# FP_Connectors.net
KiCad netlist of a schematic drawn in Altium Designer
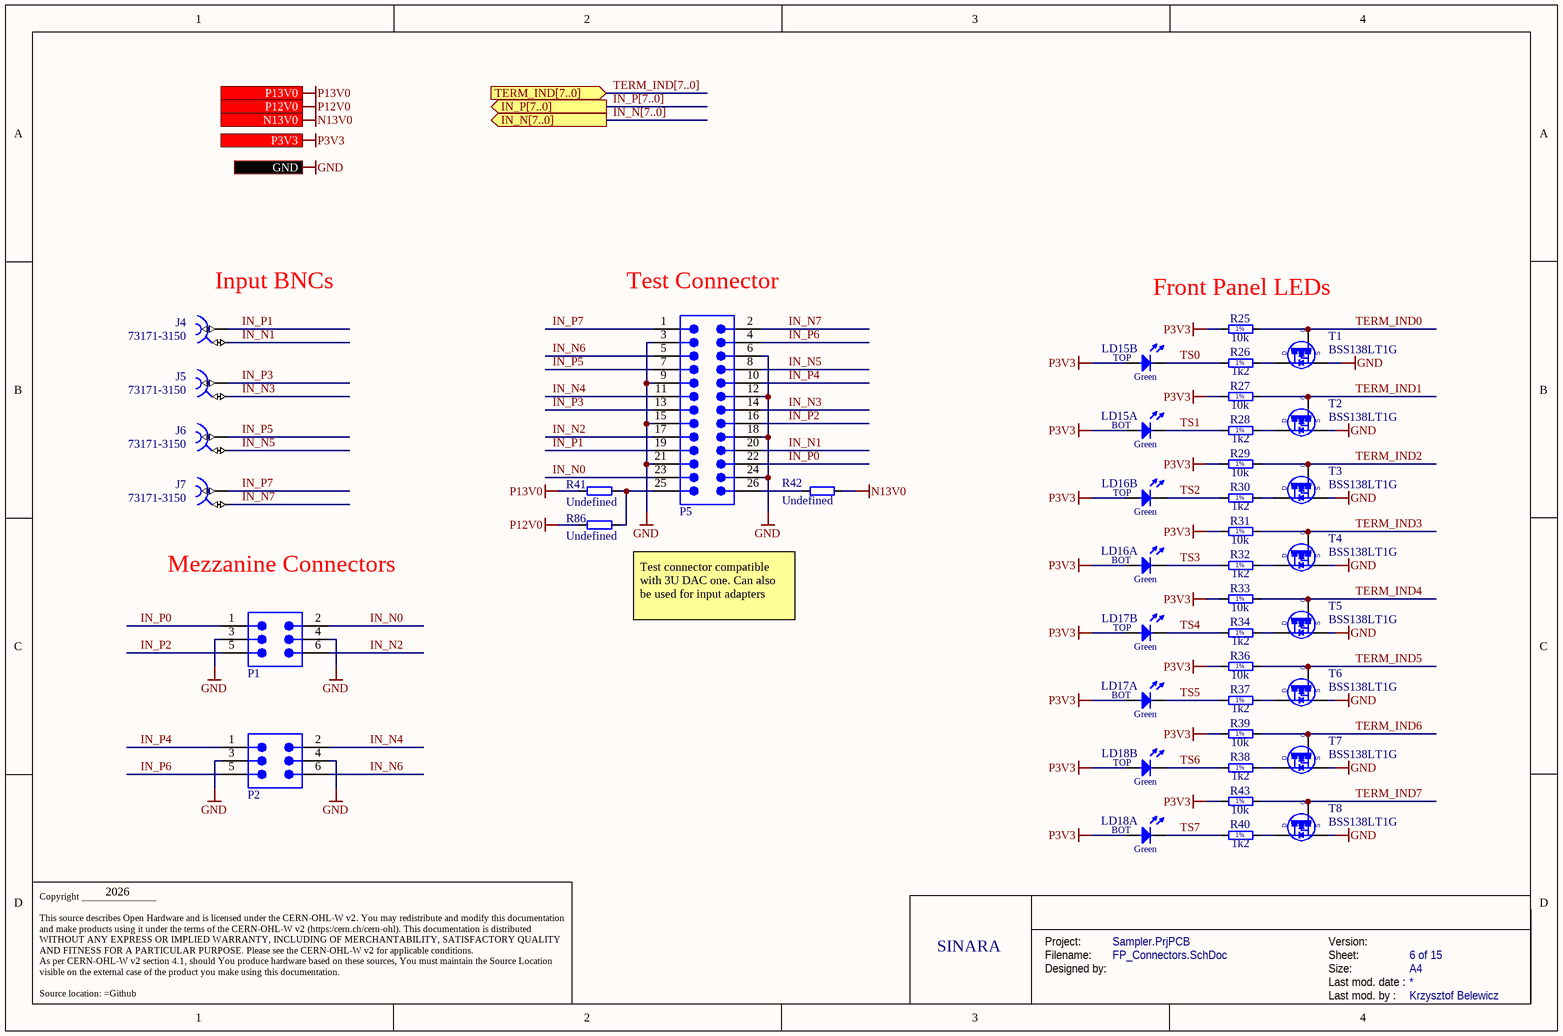
[diagram p0: FP_Connectors.SchDoc]

(export (version "E")
  (design (tool "Eeschema 10.0.6"))
  (components
    (comp (ref "J4")
      (value "73171-3150")
      (footprint "MOLEX_73171-3150")
      (description "RF Connectors / Coaxial Connectors BNC RA PCB RECPT 50 OHM")
      (fields (field (name "MANUFACTURER") "MOLEX") (field (name "MANUFACTURER PART NUMBER") "73251-3150"))
      (libsource (lib "Sampler_DIOT") (part "MOLEX_73171-3150"))
    )
    (comp (ref "J5")
      (value "73171-3150")
      (footprint "MOLEX_73171-3150")
      (description "RF Connectors / Coaxial Connectors BNC RA PCB RECPT 50 OHM")
      (fields (field (name "MANUFACTURER") "MOLEX") (field (name "MANUFACTURER PART NUMBER") "73251-3150"))
      (libsource (lib "Sampler_DIOT") (part "MOLEX_73171-3150"))
    )
    (comp (ref "J6")
      (value "73171-3150")
      (footprint "MOLEX_73171-3150")
      (description "RF Connectors / Coaxial Connectors BNC RA PCB RECPT 50 OHM")
      (fields (field (name "MANUFACTURER") "MOLEX") (field (name "MANUFACTURER PART NUMBER") "73251-3150"))
      (libsource (lib "Sampler_DIOT") (part "MOLEX_73171-3150"))
    )
    (comp (ref "J7")
      (value "73171-3150")
      (footprint "MOLEX_73171-3150")
      (description "RF Connectors / Coaxial Connectors BNC RA PCB RECPT 50 OHM")
      (fields (field (name "MANUFACTURER") "MOLEX") (field (name "MANUFACTURER PART NUMBER") "73251-3150"))
      (libsource (lib "Sampler_DIOT") (part "MOLEX_73171-3150"))
    )
    (comp (ref "LD15")
      (value "Green/Green")
      (footprint "LED_DIALIGHT_571-0122F")
      (description "LED x2 Green 1C2A-BOT_3C4A-TOP")
      (fields
        (field (name "PART NUMBER") "LED_DIALIGHT_571-0122F")
        (field (name "MANUFACTURER") "DIALIGHT")
        (field (name "AUTHOR") "CERN DEM JLC")
      )
      (libsource (lib "ICs And Semiconductors") (part "LED x2 Green 1C2A-BOT_3C4A-TOP"))
    )
    (comp (ref "LD16")
      (value "Green/Green")
      (footprint "LED_DIALIGHT_571-0122F")
      (description "LED x2 Green 1C2A-BOT_3C4A-TOP")
      (fields
        (field (name "PART NUMBER") "LED_DIALIGHT_571-0122F")
        (field (name "MANUFACTURER") "DIALIGHT")
        (field (name "AUTHOR") "CERN DEM JLC")
      )
      (libsource (lib "ICs And Semiconductors") (part "LED x2 Green 1C2A-BOT_3C4A-TOP"))
    )
    (comp (ref "LD17")
      (value "Green/Green")
      (footprint "LED_DIALIGHT_571-0122F")
      (description "LED x2 Green 1C2A-BOT_3C4A-TOP")
      (fields
        (field (name "PART NUMBER") "LED_DIALIGHT_571-0122F")
        (field (name "MANUFACTURER") "DIALIGHT")
        (field (name "AUTHOR") "CERN DEM JLC")
      )
      (libsource (lib "ICs And Semiconductors") (part "LED x2 Green 1C2A-BOT_3C4A-TOP"))
    )
    (comp (ref "LD18")
      (value "Green/Green")
      (footprint "LED_DIALIGHT_571-0122F")
      (description "LED x2 Green 1C2A-BOT_3C4A-TOP")
      (fields
        (field (name "PART NUMBER") "LED_DIALIGHT_571-0122F")
        (field (name "MANUFACTURER") "DIALIGHT")
        (field (name "AUTHOR") "CERN DEM JLC")
      )
      (libsource (lib "ICs And Semiconductors") (part "LED x2 Green 1C2A-BOT_3C4A-TOP"))
    )
    (comp (ref "P1")
      (value "61300621121")
      (footprint "61300621121")
      (description "WR-PHD Pin Header, THT, Vertical, pitch 2.54mm, 2 Row, 6P")
      (fields (field (name "MANUFACTURER") "Wurth Elektronik"))
      (libsource (lib "Altium_WR-PHD (rev24a) (4)") (part "61300621121"))
    )
    (comp (ref "P2")
      (value "61300621121")
      (footprint "61300621121")
      (description "WR-PHD Pin Header, THT, Vertical, pitch 2.54mm, 2 Row, 6P")
      (fields (field (name "MANUFACTURER") "Wurth Elektronik"))
      (libsource (lib "Altium_WR-PHD (rev24a) (4)") (part "61300621121"))
    )
    (comp (ref "P5")
      (value "61302621121")
      (footprint "61302621121")
      (description "WR-PHD Pin Header, THT, Vertical, pitch 2.54mm, 2 Row, 26P")
      (fields (field (name "MANUFACTURER") "Wurth Elektronik"))
      (libsource (lib "Altium_WR-PHD (rev24a) (4)") (part "61302621121"))
    )
    (comp (ref "R25")
      (value "10k")
      (footprint "RESC1005X40N")
      (description "Resistor - 1%")
      (fields
        (field (name "PART NUMBER") "R0402_10K_1%_0.0625W_100PPM")
        (field (name "POWER") "0.0625W")
        (field (name "AUTHOR") "CERN DEM JLC")
      )
      (libsource (lib "Resistors") (part "Resistor - 1%"))
    )
    (comp (ref "R26")
      (value "1k2")
      (footprint "RESC1608X55N")
      (description "Resistor - 1%")
      (fields
        (field (name "PART NUMBER") "R0603_1K2_1%_0.1W_100PPM")
        (field (name "POWER") "0.1W")
        (field (name "AUTHOR") "CERN DEM JLC")
      )
      (libsource (lib "Resistors") (part "Resistor - 1%"))
    )
    (comp (ref "R27")
      (value "10k")
      (footprint "RESC1005X40N")
      (description "Resistor - 1%")
      (fields
        (field (name "PART NUMBER") "R0402_10K_1%_0.0625W_100PPM")
        (field (name "POWER") "0.0625W")
        (field (name "AUTHOR") "CERN DEM JLC")
      )
      (libsource (lib "Resistors") (part "Resistor - 1%"))
    )
    (comp (ref "R28")
      (value "1k2")
      (footprint "RESC1608X55N")
      (description "Resistor - 1%")
      (fields
        (field (name "PART NUMBER") "R0603_1K2_1%_0.1W_100PPM")
        (field (name "POWER") "0.1W")
        (field (name "AUTHOR") "CERN DEM JLC")
      )
      (libsource (lib "Resistors") (part "Resistor - 1%"))
    )
    (comp (ref "R29")
      (value "10k")
      (footprint "RESC1005X40N")
      (description "Resistor - 1%")
      (fields
        (field (name "PART NUMBER") "R0402_10K_1%_0.0625W_100PPM")
        (field (name "POWER") "0.0625W")
        (field (name "AUTHOR") "CERN DEM JLC")
      )
      (libsource (lib "Resistors") (part "Resistor - 1%"))
    )
    (comp (ref "R30")
      (value "1k2")
      (footprint "RESC1608X55N")
      (description "Resistor - 1%")
      (fields
        (field (name "PART NUMBER") "R0603_1K2_1%_0.1W_100PPM")
        (field (name "POWER") "0.1W")
        (field (name "AUTHOR") "CERN DEM JLC")
      )
      (libsource (lib "Resistors") (part "Resistor - 1%"))
    )
    (comp (ref "R31")
      (value "10k")
      (footprint "RESC1005X40N")
      (description "Resistor - 1%")
      (fields
        (field (name "PART NUMBER") "R0402_10K_1%_0.0625W_100PPM")
        (field (name "POWER") "0.0625W")
        (field (name "AUTHOR") "CERN DEM JLC")
      )
      (libsource (lib "Resistors") (part "Resistor - 1%"))
    )
    (comp (ref "R32")
      (value "1k2")
      (footprint "RESC1608X55N")
      (description "Resistor - 1%")
      (fields
        (field (name "PART NUMBER") "R0603_1K2_1%_0.1W_100PPM")
        (field (name "POWER") "0.1W")
        (field (name "AUTHOR") "CERN DEM JLC")
      )
      (libsource (lib "Resistors") (part "Resistor - 1%"))
    )
    (comp (ref "R33")
      (value "10k")
      (footprint "RESC1005X40N")
      (description "Resistor - 1%")
      (fields
        (field (name "PART NUMBER") "R0402_10K_1%_0.0625W_100PPM")
        (field (name "POWER") "0.0625W")
        (field (name "AUTHOR") "CERN DEM JLC")
      )
      (libsource (lib "Resistors") (part "Resistor - 1%"))
    )
    (comp (ref "R34")
      (value "1k2")
      (footprint "RESC1608X55N")
      (description "Resistor - 1%")
      (fields
        (field (name "PART NUMBER") "R0603_1K2_1%_0.1W_100PPM")
        (field (name "POWER") "0.1W")
        (field (name "AUTHOR") "CERN DEM JLC")
      )
      (libsource (lib "Resistors") (part "Resistor - 1%"))
    )
    (comp (ref "R36")
      (value "10k")
      (footprint "RESC1005X40N")
      (description "Resistor - 1%")
      (fields
        (field (name "PART NUMBER") "R0402_10K_1%_0.0625W_100PPM")
        (field (name "POWER") "0.0625W")
        (field (name "AUTHOR") "CERN DEM JLC")
      )
      (libsource (lib "Resistors") (part "Resistor - 1%"))
    )
    (comp (ref "R37")
      (value "1k2")
      (footprint "RESC1608X55N")
      (description "Resistor - 1%")
      (fields
        (field (name "PART NUMBER") "R0603_1K2_1%_0.1W_100PPM")
        (field (name "POWER") "0.1W")
        (field (name "AUTHOR") "CERN DEM JLC")
      )
      (libsource (lib "Resistors") (part "Resistor - 1%"))
    )
    (comp (ref "R38")
      (value "1k2")
      (footprint "RESC1608X55N")
      (description "Resistor - 1%")
      (fields
        (field (name "PART NUMBER") "R0603_1K2_1%_0.1W_100PPM")
        (field (name "POWER") "0.1W")
        (field (name "AUTHOR") "CERN DEM JLC")
      )
      (libsource (lib "Resistors") (part "Resistor - 1%"))
    )
    (comp (ref "R39")
      (value "10k")
      (footprint "RESC1005X40N")
      (description "Resistor - 1%")
      (fields
        (field (name "PART NUMBER") "R0402_10K_1%_0.0625W_100PPM")
        (field (name "POWER") "0.0625W")
        (field (name "AUTHOR") "CERN DEM JLC")
      )
      (libsource (lib "Resistors") (part "Resistor - 1%"))
    )
    (comp (ref "R40")
      (value "1k2")
      (footprint "RESC1608X55N")
      (description "Resistor - 1%")
      (fields
        (field (name "PART NUMBER") "R0603_1K2_1%_0.1W_100PPM")
        (field (name "POWER") "0.1W")
        (field (name "AUTHOR") "CERN DEM JLC")
      )
      (libsource (lib "Resistors") (part "Resistor - 1%"))
    )
    (comp (ref "R41")
      (value "Undefined")
      (footprint "RESC1608X55N")
      (description "Resistor")
      (fields (field (name "PART NUMBER") "R0603_NO-VALUE") (field (name "AUTHOR") "CERN DEM JLC"))
      (libsource (lib "Resistors") (part "Resistor"))
    )
    (comp (ref "R42")
      (value "Undefined")
      (footprint "RESC1608X55N")
      (description "Resistor")
      (fields (field (name "PART NUMBER") "R0603_NO-VALUE") (field (name "AUTHOR") "CERN DEM JLC"))
      (libsource (lib "Resistors") (part "Resistor"))
    )
    (comp (ref "R43")
      (value "10k")
      (footprint "RESC1005X40N")
      (description "Resistor - 1%")
      (fields
        (field (name "PART NUMBER") "R0402_10K_1%_0.0625W_100PPM")
        (field (name "POWER") "0.0625W")
        (field (name "AUTHOR") "CERN DEM JLC")
      )
      (libsource (lib "Resistors") (part "Resistor - 1%"))
    )
    (comp (ref "R86")
      (value "Undefined")
      (footprint "RESC1608X55N")
      (description "Resistor")
      (fields (field (name "PART NUMBER") "R0603_NO-VALUE") (field (name "AUTHOR") "CERN DEM JLC"))
      (libsource (lib "Resistors") (part "Resistor"))
    )
    (comp (ref "T1")
      (value "BSS138LT1G")
      (footprint "SOT95P240X110-3N")
      (description "N-CHANNEL MOSFET WITH DIODE")
      (fields (field (name "MANUFACTURER") "ON SEMICONDUCTOR") (field (name "AUTHOR") "CERN DEM JLC"))
      (libsource (lib "ICs And Semiconductors") (part "N-MOSFET-D 1G 2S 3D"))
    )
    (comp (ref "T2")
      (value "BSS138LT1G")
      (footprint "SOT95P240X110-3N")
      (description "N-CHANNEL MOSFET WITH DIODE")
      (fields (field (name "MANUFACTURER") "ON SEMICONDUCTOR") (field (name "AUTHOR") "CERN DEM JLC"))
      (libsource (lib "ICs And Semiconductors") (part "N-MOSFET-D 1G 2S 3D"))
    )
    (comp (ref "T3")
      (value "BSS138LT1G")
      (footprint "SOT95P240X110-3N")
      (description "N-CHANNEL MOSFET WITH DIODE")
      (fields (field (name "MANUFACTURER") "ON SEMICONDUCTOR") (field (name "AUTHOR") "CERN DEM JLC"))
      (libsource (lib "ICs And Semiconductors") (part "N-MOSFET-D 1G 2S 3D"))
    )
    (comp (ref "T4")
      (value "BSS138LT1G")
      (footprint "SOT95P240X110-3N")
      (description "N-CHANNEL MOSFET WITH DIODE")
      (fields (field (name "MANUFACTURER") "ON SEMICONDUCTOR") (field (name "AUTHOR") "CERN DEM JLC"))
      (libsource (lib "ICs And Semiconductors") (part "N-MOSFET-D 1G 2S 3D"))
    )
    (comp (ref "T5")
      (value "BSS138LT1G")
      (footprint "SOT95P240X110-3N")
      (description "N-CHANNEL MOSFET WITH DIODE")
      (fields (field (name "MANUFACTURER") "ON SEMICONDUCTOR") (field (name "AUTHOR") "CERN DEM JLC"))
      (libsource (lib "ICs And Semiconductors") (part "N-MOSFET-D 1G 2S 3D"))
    )
    (comp (ref "T6")
      (value "BSS138LT1G")
      (footprint "SOT95P240X110-3N")
      (description "N-CHANNEL MOSFET WITH DIODE")
      (fields (field (name "MANUFACTURER") "ON SEMICONDUCTOR") (field (name "AUTHOR") "CERN DEM JLC"))
      (libsource (lib "ICs And Semiconductors") (part "N-MOSFET-D 1G 2S 3D"))
    )
    (comp (ref "T7")
      (value "BSS138LT1G")
      (footprint "SOT95P240X110-3N")
      (description "N-CHANNEL MOSFET WITH DIODE")
      (fields (field (name "MANUFACTURER") "ON SEMICONDUCTOR") (field (name "AUTHOR") "CERN DEM JLC"))
      (libsource (lib "ICs And Semiconductors") (part "N-MOSFET-D 1G 2S 3D"))
    )
    (comp (ref "T8")
      (value "BSS138LT1G")
      (footprint "SOT95P240X110-3N")
      (description "N-CHANNEL MOSFET WITH DIODE")
      (fields (field (name "MANUFACTURER") "ON SEMICONDUCTOR") (field (name "AUTHOR") "CERN DEM JLC"))
      (libsource (lib "ICs And Semiconductors") (part "N-MOSFET-D 1G 2S 3D"))
    )
  )
  (nets
    (net (code "1") (name "/IN_N0") (class "Default")
      (node (ref "P1") (pin "2") (pinfunction "2_2") (pintype "passive"))
      (node (ref "P5") (pin "23") (pinfunction "23_23") (pintype "passive"))
    )
    (net (code "2") (name "/IN_N1") (class "Default")
      (node (ref "J4") (pin "2") (pinfunction "2_2") (pintype "bidirectional"))
      (node (ref "P5") (pin "20") (pinfunction "20_20") (pintype "passive"))
    )
    (net (code "3") (name "/IN_N2") (class "Default")
      (node (ref "P1") (pin "6") (pinfunction "6_6") (pintype "passive"))
      (node (ref "P5") (pin "17") (pinfunction "17_17") (pintype "passive"))
    )
    (net (code "4") (name "/IN_N3") (class "Default")
      (node (ref "J5") (pin "2") (pinfunction "2_2") (pintype "bidirectional"))
      (node (ref "P5") (pin "14") (pinfunction "14_14") (pintype "passive"))
    )
    (net (code "5") (name "/IN_N4") (class "Default")
      (node (ref "P2") (pin "2") (pinfunction "2_2") (pintype "passive"))
      (node (ref "P5") (pin "11") (pinfunction "11_11") (pintype "passive"))
    )
    (net (code "6") (name "/IN_N5") (class "Default")
      (node (ref "J6") (pin "2") (pinfunction "2_2") (pintype "bidirectional"))
      (node (ref "P5") (pin "8") (pinfunction "8_8") (pintype "passive"))
    )
    (net (code "7") (name "/IN_N6") (class "Default")
      (node (ref "P2") (pin "6") (pinfunction "6_6") (pintype "passive"))
      (node (ref "P5") (pin "5") (pinfunction "5_5") (pintype "passive"))
    )
    (net (code "8") (name "/IN_N7") (class "Default")
      (node (ref "J7") (pin "2") (pinfunction "2_2") (pintype "bidirectional"))
      (node (ref "P5") (pin "2") (pinfunction "2_2") (pintype "passive"))
    )
    (net (code "10") (name "/IN_P0") (class "Default")
      (node (ref "P1") (pin "1") (pinfunction "1_1") (pintype "passive"))
      (node (ref "P5") (pin "22") (pinfunction "22_22") (pintype "passive"))
    )
    (net (code "11") (name "/IN_P1") (class "Default")
      (node (ref "J4") (pin "1") (pinfunction "1_1") (pintype "bidirectional"))
      (node (ref "P5") (pin "19") (pinfunction "19_19") (pintype "passive"))
    )
    (net (code "12") (name "/IN_P2") (class "Default")
      (node (ref "P1") (pin "5") (pinfunction "5_5") (pintype "passive"))
      (node (ref "P5") (pin "16") (pinfunction "16_16") (pintype "passive"))
    )
    (net (code "13") (name "/IN_P3") (class "Default")
      (node (ref "J5") (pin "1") (pinfunction "1_1") (pintype "bidirectional"))
      (node (ref "P5") (pin "13") (pinfunction "13_13") (pintype "passive"))
    )
    (net (code "14") (name "/IN_P4") (class "Default")
      (node (ref "P2") (pin "1") (pinfunction "1_1") (pintype "passive"))
      (node (ref "P5") (pin "10") (pinfunction "10_10") (pintype "passive"))
    )
    (net (code "15") (name "/IN_P5") (class "Default")
      (node (ref "J6") (pin "1") (pinfunction "1_1") (pintype "bidirectional"))
      (node (ref "P5") (pin "7") (pinfunction "7_7") (pintype "passive"))
    )
    (net (code "16") (name "/IN_P6") (class "Default")
      (node (ref "P2") (pin "5") (pinfunction "5_5") (pintype "passive"))
      (node (ref "P5") (pin "4") (pinfunction "4_4") (pintype "passive"))
    )
    (net (code "17") (name "/IN_P7") (class "Default")
      (node (ref "J7") (pin "1") (pinfunction "1_1") (pintype "bidirectional"))
      (node (ref "P5") (pin "1") (pinfunction "1_1") (pintype "passive"))
    )
    (net (code "19") (name "/TERM_IND0") (class "Default")
      (node (ref "R25") (pin "2") (pinfunction "2_2") (pintype "passive"))
      (node (ref "T1") (pin "1") (pinfunction "G_1") (pintype "passive"))
    )
    (net (code "20") (name "/TERM_IND1") (class "Default")
      (node (ref "R27") (pin "2") (pinfunction "2_2") (pintype "passive"))
      (node (ref "T2") (pin "1") (pinfunction "G_1") (pintype "passive"))
    )
    (net (code "21") (name "/TERM_IND2") (class "Default")
      (node (ref "R29") (pin "2") (pinfunction "2_2") (pintype "passive"))
      (node (ref "T3") (pin "1") (pinfunction "G_1") (pintype "passive"))
    )
    (net (code "22") (name "/TERM_IND3") (class "Default")
      (node (ref "R31") (pin "2") (pinfunction "2_2") (pintype "passive"))
      (node (ref "T4") (pin "1") (pinfunction "G_1") (pintype "passive"))
    )
    (net (code "23") (name "/TERM_IND4") (class "Default")
      (node (ref "R33") (pin "2") (pinfunction "2_2") (pintype "passive"))
      (node (ref "T5") (pin "1") (pinfunction "G_1") (pintype "passive"))
    )
    (net (code "24") (name "/TERM_IND5") (class "Default")
      (node (ref "R36") (pin "2") (pinfunction "2_2") (pintype "passive"))
      (node (ref "T6") (pin "1") (pinfunction "G_1") (pintype "passive"))
    )
    (net (code "25") (name "/TERM_IND6") (class "Default")
      (node (ref "R39") (pin "2") (pinfunction "2_2") (pintype "passive"))
      (node (ref "T7") (pin "1") (pinfunction "G_1") (pintype "passive"))
    )
    (net (code "26") (name "/TERM_IND7") (class "Default")
      (node (ref "R43") (pin "2") (pinfunction "2_2") (pintype "passive"))
      (node (ref "T8") (pin "1") (pinfunction "G_1") (pintype "passive"))
    )
    (net (code "28") (name "/TS0") (class "Default")
      (node (ref "LD15") (pin "3") (pinfunction "C_3") (pintype "passive"))
      (node (ref "R26") (pin "1") (pinfunction "1_1") (pintype "passive"))
    )
    (net (code "29") (name "/TS1") (class "Default")
      (node (ref "LD15") (pin "1") (pinfunction "C_1") (pintype "passive"))
      (node (ref "R28") (pin "1") (pinfunction "1_1") (pintype "passive"))
    )
    (net (code "30") (name "/TS2") (class "Default")
      (node (ref "LD16") (pin "3") (pinfunction "C_3") (pintype "passive"))
      (node (ref "R30") (pin "1") (pinfunction "1_1") (pintype "passive"))
    )
    (net (code "31") (name "/TS3") (class "Default")
      (node (ref "LD16") (pin "1") (pinfunction "C_1") (pintype "passive"))
      (node (ref "R32") (pin "1") (pinfunction "1_1") (pintype "passive"))
    )
    (net (code "32") (name "/TS4") (class "Default")
      (node (ref "LD17") (pin "3") (pinfunction "C_3") (pintype "passive"))
      (node (ref "R34") (pin "1") (pinfunction "1_1") (pintype "passive"))
    )
    (net (code "33") (name "/TS5") (class "Default")
      (node (ref "LD17") (pin "1") (pinfunction "C_1") (pintype "passive"))
      (node (ref "R37") (pin "1") (pinfunction "1_1") (pintype "passive"))
    )
    (net (code "34") (name "/TS6") (class "Default")
      (node (ref "LD18") (pin "3") (pinfunction "C_3") (pintype "passive"))
      (node (ref "R38") (pin "1") (pinfunction "1_1") (pintype "passive"))
    )
    (net (code "35") (name "/TS7") (class "Default")
      (node (ref "LD18") (pin "1") (pinfunction "C_1") (pintype "passive"))
      (node (ref "R40") (pin "1") (pinfunction "1_1") (pintype "passive"))
    )
    (net (code "36") (name "GND") (class "Default")
      (node (ref "P1") (pin "3") (pinfunction "3_3") (pintype "passive"))
      (node (ref "P1") (pin "4") (pinfunction "4_4") (pintype "passive"))
      (node (ref "P2") (pin "3") (pinfunction "3_3") (pintype "passive"))
      (node (ref "P2") (pin "4") (pinfunction "4_4") (pintype "passive"))
      (node (ref "P5") (pin "12") (pinfunction "12_12") (pintype "passive"))
      (node (ref "P5") (pin "15") (pinfunction "15_15") (pintype "passive"))
      (node (ref "P5") (pin "18") (pinfunction "18_18") (pintype "passive"))
      (node (ref "P5") (pin "21") (pinfunction "21_21") (pintype "passive"))
      (node (ref "P5") (pin "24") (pinfunction "24_24") (pintype "passive"))
      (node (ref "P5") (pin "3") (pinfunction "3_3") (pintype "passive"))
      (node (ref "P5") (pin "6") (pinfunction "6_6") (pintype "passive"))
      (node (ref "P5") (pin "9") (pinfunction "9_9") (pintype "passive"))
      (node (ref "T1") (pin "2") (pinfunction "S_2") (pintype "passive"))
      (node (ref "T2") (pin "2") (pinfunction "S_2") (pintype "passive"))
      (node (ref "T3") (pin "2") (pinfunction "S_2") (pintype "passive"))
      (node (ref "T4") (pin "2") (pinfunction "S_2") (pintype "passive"))
      (node (ref "T5") (pin "2") (pinfunction "S_2") (pintype "passive"))
      (node (ref "T6") (pin "2") (pinfunction "S_2") (pintype "passive"))
      (node (ref "T7") (pin "2") (pinfunction "S_2") (pintype "passive"))
      (node (ref "T8") (pin "2") (pinfunction "S_2") (pintype "passive"))
    )
    (net (code "37") (name "N13V0") (class "Default")
      (node (ref "R42") (pin "2") (pinfunction "2_2") (pintype "passive"))
    )
    (net (code "38") (name "Net-(P5-Pad25)") (class "Default")
      (node (ref "P5") (pin "25") (pinfunction "25_25") (pintype "passive"))
      (node (ref "R41") (pin "1") (pinfunction "1_1") (pintype "passive"))
      (node (ref "R86") (pin "1") (pinfunction "1_1") (pintype "passive"))
    )
    (net (code "39") (name "Net-(P5-Pad26)") (class "Default")
      (node (ref "P5") (pin "26") (pinfunction "26_26") (pintype "passive"))
      (node (ref "R42") (pin "1") (pinfunction "1_1") (pintype "passive"))
    )
    (net (code "40") (name "Net-(T1-D)") (class "Default")
      (node (ref "R26") (pin "2") (pinfunction "2_2") (pintype "passive"))
      (node (ref "T1") (pin "3") (pinfunction "D_3") (pintype "passive"))
    )
    (net (code "41") (name "Net-(T2-D)") (class "Default")
      (node (ref "R28") (pin "2") (pinfunction "2_2") (pintype "passive"))
      (node (ref "T2") (pin "3") (pinfunction "D_3") (pintype "passive"))
    )
    (net (code "42") (name "Net-(T3-D)") (class "Default")
      (node (ref "R30") (pin "2") (pinfunction "2_2") (pintype "passive"))
      (node (ref "T3") (pin "3") (pinfunction "D_3") (pintype "passive"))
    )
    (net (code "43") (name "Net-(T4-D)") (class "Default")
      (node (ref "R32") (pin "2") (pinfunction "2_2") (pintype "passive"))
      (node (ref "T4") (pin "3") (pinfunction "D_3") (pintype "passive"))
    )
    (net (code "44") (name "Net-(T5-D)") (class "Default")
      (node (ref "R34") (pin "2") (pinfunction "2_2") (pintype "passive"))
      (node (ref "T5") (pin "3") (pinfunction "D_3") (pintype "passive"))
    )
    (net (code "45") (name "Net-(T6-D)") (class "Default")
      (node (ref "R37") (pin "2") (pinfunction "2_2") (pintype "passive"))
      (node (ref "T6") (pin "3") (pinfunction "D_3") (pintype "passive"))
    )
    (net (code "46") (name "Net-(T7-D)") (class "Default")
      (node (ref "R38") (pin "2") (pinfunction "2_2") (pintype "passive"))
      (node (ref "T7") (pin "3") (pinfunction "D_3") (pintype "passive"))
    )
    (net (code "47") (name "Net-(T8-D)") (class "Default")
      (node (ref "R40") (pin "2") (pinfunction "2_2") (pintype "passive"))
      (node (ref "T8") (pin "3") (pinfunction "D_3") (pintype "passive"))
    )
    (net (code "48") (name "P3V3") (class "Default")
      (node (ref "LD15") (pin "2") (pinfunction "A_2") (pintype "passive"))
      (node (ref "LD15") (pin "4") (pinfunction "A_4") (pintype "passive"))
      (node (ref "LD16") (pin "2") (pinfunction "A_2") (pintype "passive"))
      (node (ref "LD16") (pin "4") (pinfunction "A_4") (pintype "passive"))
      (node (ref "LD17") (pin "2") (pinfunction "A_2") (pintype "passive"))
      (node (ref "LD17") (pin "4") (pinfunction "A_4") (pintype "passive"))
      (node (ref "LD18") (pin "2") (pinfunction "A_2") (pintype "passive"))
      (node (ref "LD18") (pin "4") (pinfunction "A_4") (pintype "passive"))
      (node (ref "R25") (pin "1") (pinfunction "1_1") (pintype "passive"))
      (node (ref "R27") (pin "1") (pinfunction "1_1") (pintype "passive"))
      (node (ref "R29") (pin "1") (pinfunction "1_1") (pintype "passive"))
      (node (ref "R31") (pin "1") (pinfunction "1_1") (pintype "passive"))
      (node (ref "R33") (pin "1") (pinfunction "1_1") (pintype "passive"))
      (node (ref "R36") (pin "1") (pinfunction "1_1") (pintype "passive"))
      (node (ref "R39") (pin "1") (pinfunction "1_1") (pintype "passive"))
      (node (ref "R43") (pin "1") (pinfunction "1_1") (pintype "passive"))
    )
    (net (code "49") (name "P12V0") (class "Default")
      (node (ref "R86") (pin "2") (pinfunction "2_2") (pintype "passive"))
    )
    (net (code "50") (name "P13V0") (class "Default")
      (node (ref "R41") (pin "2") (pinfunction "2_2") (pintype "passive"))
    )
  )
)
